# BatteryTestBoard_V1.net
KiCad netlist of a schematic drawn in EAGLE
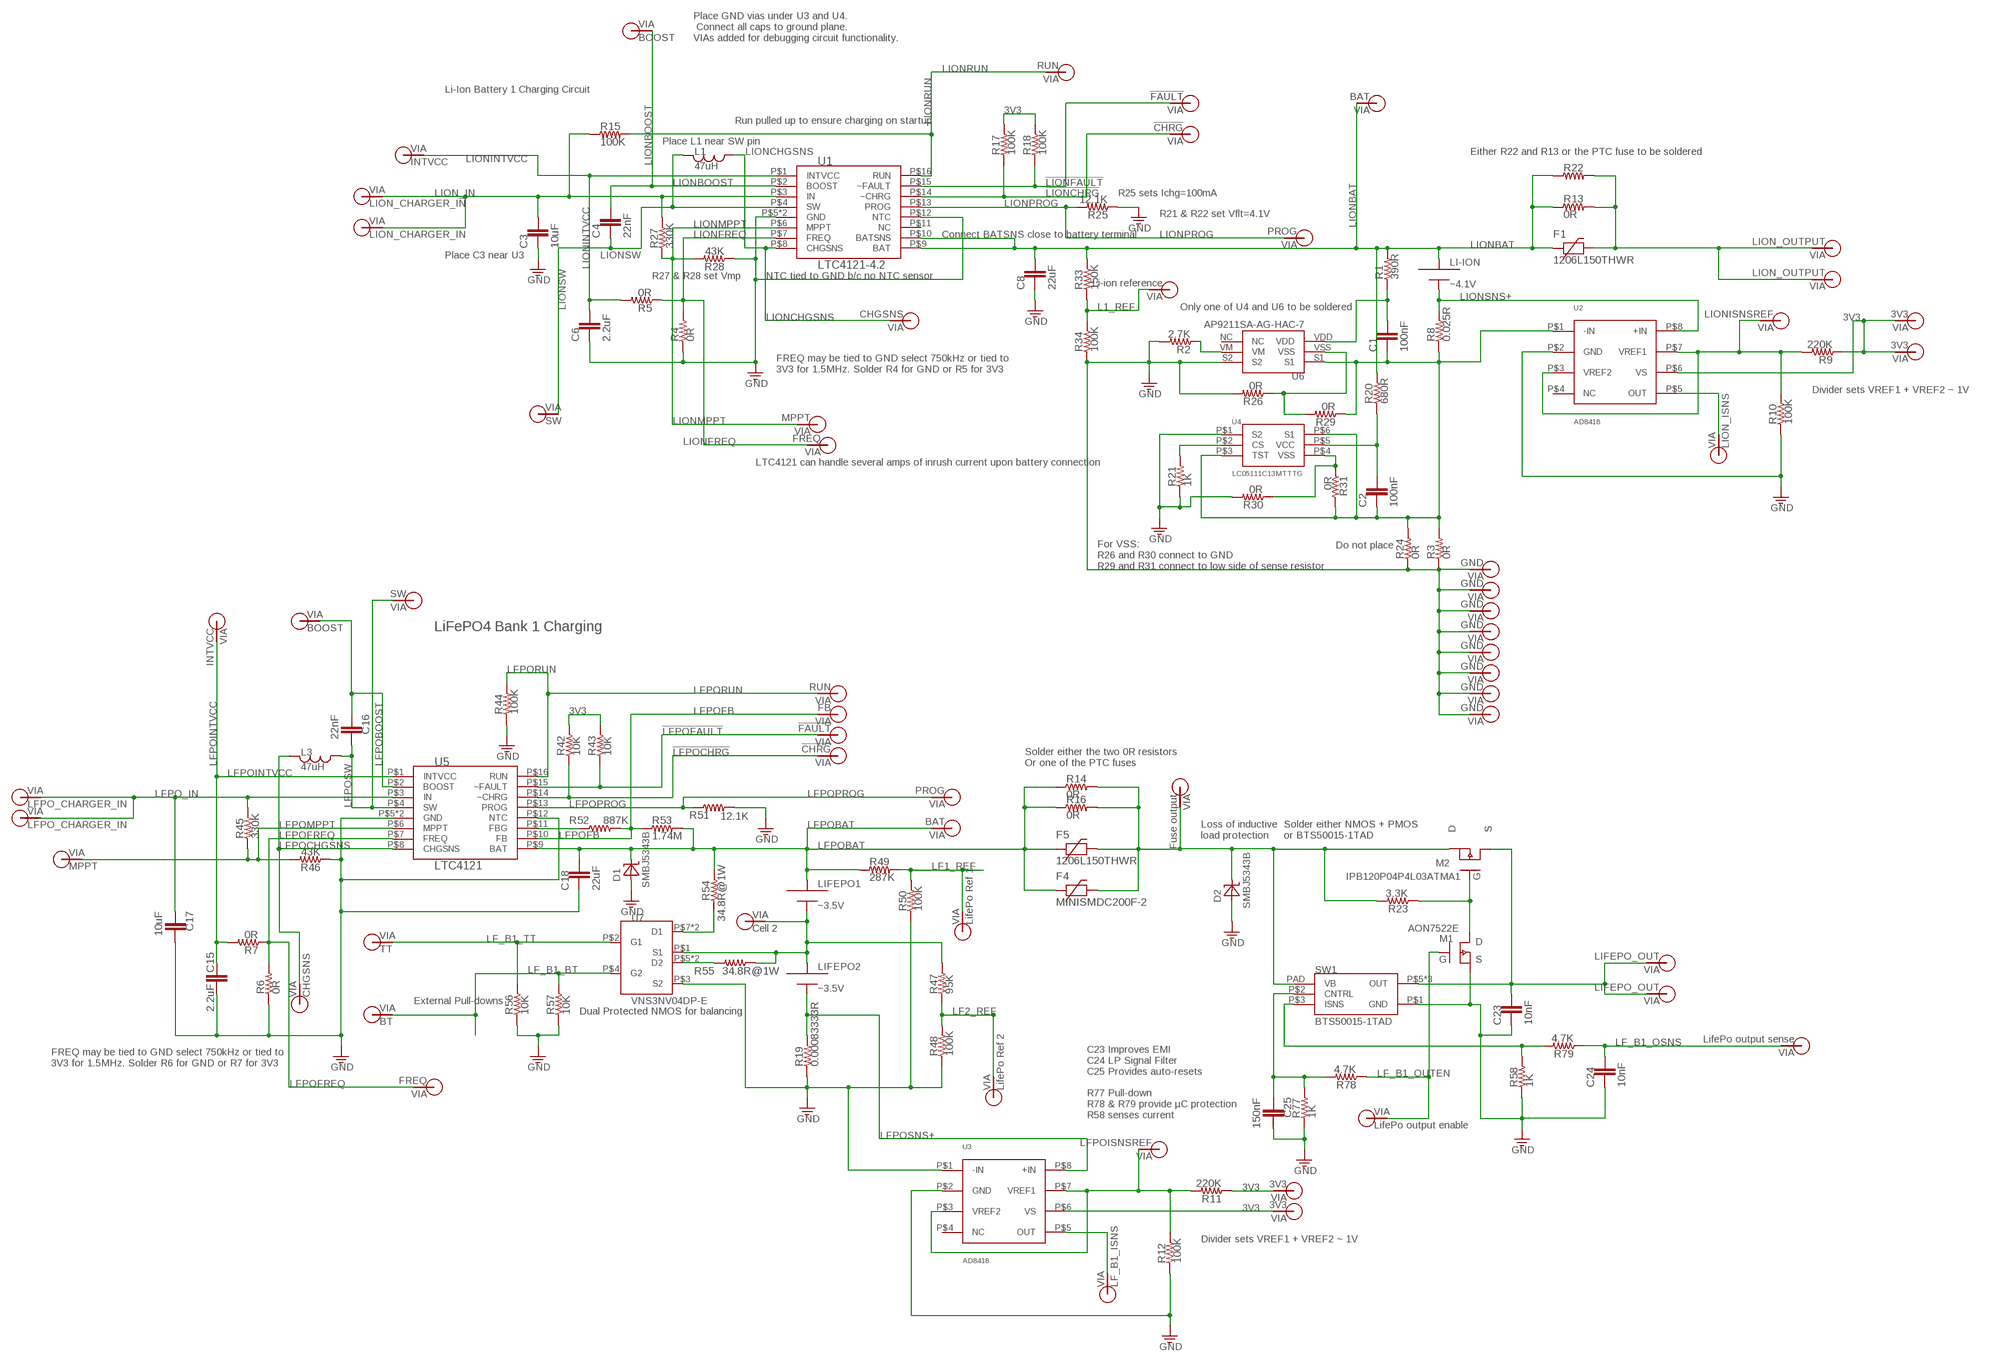
[diagram p0: schematic, sheet 1]

(export (version "E")
  (design (tool "Eeschema 10.0.6"))
  (components
    (comp (ref "C1")
      (value "100nF")
      (footprint "eagle-import:0805")
      (libsource (lib "eagle-import") (part "CAP0805"))
    )
    (comp (ref "C2")
      (value "100nF")
      (footprint "eagle-import:0805")
      (libsource (lib "eagle-import") (part "CAP0805"))
    )
    (comp (ref "C3")
      (value "10uF")
      (footprint "eagle-import:0805")
      (libsource (lib "eagle-import") (part "CAP0805"))
    )
    (comp (ref "C4")
      (value "22nF")
      (footprint "eagle-import:0805")
      (libsource (lib "eagle-import") (part "CAP0805"))
    )
    (comp (ref "C6")
      (value "2.2uF")
      (footprint "eagle-import:0805")
      (libsource (lib "eagle-import") (part "CAP0805"))
    )
    (comp (ref "C8")
      (value "22uF")
      (footprint "eagle-import:0805")
      (libsource (lib "eagle-import") (part "CAP0805"))
    )
    (comp (ref "C15")
      (value "2.2uF")
      (footprint "eagle-import:0805")
      (libsource (lib "eagle-import") (part "CAP0805"))
    )
    (comp (ref "C16")
      (value "22nF")
      (footprint "eagle-import:0805")
      (libsource (lib "eagle-import") (part "CAP0805"))
    )
    (comp (ref "C17")
      (value "10uF")
      (footprint "eagle-import:0805")
      (libsource (lib "eagle-import") (part "CAP0805"))
    )
    (comp (ref "C18")
      (value "22uF")
      (footprint "eagle-import:0805")
      (libsource (lib "eagle-import") (part "CAP0805"))
    )
    (comp (ref "C23")
      (value "10nF")
      (footprint "eagle-import:0805")
      (libsource (lib "eagle-import") (part "CAP0805"))
    )
    (comp (ref "C24")
      (value "10nF")
      (footprint "eagle-import:0805")
      (libsource (lib "eagle-import") (part "CAP0805"))
    )
    (comp (ref "C25")
      (value "150nF")
      (footprint "eagle-import:0805")
      (libsource (lib "eagle-import") (part "CAP0805"))
    )
    (comp (ref "D1")
      (value "SMBJ5343B")
      (footprint "eagle-import:DO214AA")
      (libsource (lib "eagle-import") (part "SMBJ5343B"))
    )
    (comp (ref "D2")
      (value "SMBJ5343B")
      (footprint "eagle-import:DO214AA")
      (libsource (lib "eagle-import") (part "SMBJ5343B"))
    )
    (comp (ref "F1")
      (value "1206L150THWR")
      (footprint "eagle-import:1206")
      (libsource (lib "eagle-import") (part "1206L150THWR"))
    )
    (comp (ref "F4")
      (value "MINISMDC200F-2")
      (footprint "eagle-import:1812")
      (libsource (lib "eagle-import") (part "MINISMDC200F-2"))
    )
    (comp (ref "F5")
      (value "1206L150THWR")
      (footprint "eagle-import:1206")
      (libsource (lib "eagle-import") (part "1206L150THWR"))
    )
    (comp (ref "L1")
      (value "47uH")
      (footprint "eagle-import:1812")
      (libsource (lib "eagle-import") (part "IND1812"))
    )
    (comp (ref "L3")
      (value "47uH")
      (footprint "eagle-import:1812")
      (libsource (lib "eagle-import") (part "IND1812"))
    )
    (comp (ref "LI-ION")
      (value "~4.1V")
      (footprint "eagle-import:EQUISAT-BATTERY-VA")
      (libsource (lib "eagle-import") (part "LI-ION"))
    )
    (comp (ref "LIFEPO1")
      (value "~3.5V")
      (footprint "eagle-import:EQUISAT-BATTERY-VA")
      (libsource (lib "eagle-import") (part "LIFEPO4VA"))
    )
    (comp (ref "LIFEPO2")
      (value "~3.5V")
      (footprint "eagle-import:EQUISAT-BATTERY-VA")
      (libsource (lib "eagle-import") (part "LIFEPO4VA"))
    )
    (comp (ref "M1")
      (value "AON7522E")
      (footprint "eagle-import:DFN-3X3-8")
      (libsource (lib "eagle-import") (part "AON7522E"))
    )
    (comp (ref "M2")
      (value "IPB120P04P4L03ATMA1")
      (footprint "eagle-import:TO263")
      (libsource (lib "eagle-import") (part "IPB120P04P4L03ATMA1"))
    )
    (comp (ref "R1")
      (value "390R")
      (footprint "eagle-import:0805")
      (libsource (lib "eagle-import") (part "RES0805"))
    )
    (comp (ref "R2")
      (value "2.7K")
      (footprint "eagle-import:0805")
      (libsource (lib "eagle-import") (part "RES0805"))
    )
    (comp (ref "R3")
      (value "0R")
      (footprint "eagle-import:1210")
      (libsource (lib "eagle-import") (part "RES1210"))
    )
    (comp (ref "R4")
      (value "0R")
      (footprint "eagle-import:0805")
      (libsource (lib "eagle-import") (part "RES0805"))
    )
    (comp (ref "R5")
      (value "0R")
      (footprint "eagle-import:0805")
      (libsource (lib "eagle-import") (part "RES0805"))
    )
    (comp (ref "R6")
      (value "0R")
      (footprint "eagle-import:0805")
      (libsource (lib "eagle-import") (part "RES0805"))
    )
    (comp (ref "R7")
      (value "0R")
      (footprint "eagle-import:0805")
      (libsource (lib "eagle-import") (part "RES0805"))
    )
    (comp (ref "R8")
      (value "0.025R")
      (footprint "eagle-import:1210")
      (libsource (lib "eagle-import") (part "RES1210"))
    )
    (comp (ref "R9")
      (value "220K")
      (footprint "eagle-import:0805")
      (libsource (lib "eagle-import") (part "RES0805"))
    )
    (comp (ref "R10")
      (value "100K")
      (footprint "eagle-import:0805")
      (libsource (lib "eagle-import") (part "RES0805"))
    )
    (comp (ref "R11")
      (value "220K")
      (footprint "eagle-import:0805")
      (libsource (lib "eagle-import") (part "RES0805"))
    )
    (comp (ref "R12")
      (value "100K")
      (footprint "eagle-import:0805")
      (libsource (lib "eagle-import") (part "RES0805"))
    )
    (comp (ref "R13")
      (value "0R")
      (footprint "eagle-import:1210")
      (libsource (lib "eagle-import") (part "RES1210"))
    )
    (comp (ref "R14")
      (value "0R")
      (footprint "eagle-import:1210")
      (libsource (lib "eagle-import") (part "RES1210"))
    )
    (comp (ref "R15")
      (value "100K")
      (footprint "eagle-import:0805")
      (libsource (lib "eagle-import") (part "RES0805"))
    )
    (comp (ref "R16")
      (value "0R")
      (footprint "eagle-import:1210")
      (libsource (lib "eagle-import") (part "RES1210"))
    )
    (comp (ref "R17")
      (value "100K")
      (footprint "eagle-import:0805")
      (libsource (lib "eagle-import") (part "RES0805"))
    )
    (comp (ref "R18")
      (value "100K")
      (footprint "eagle-import:0805")
      (libsource (lib "eagle-import") (part "RES0805"))
    )
    (comp (ref "R19")
      (value "0.00083333R")
      (footprint "eagle-import:1210")
      (libsource (lib "eagle-import") (part "RES1210"))
    )
    (comp (ref "R20")
      (value "680R")
      (footprint "eagle-import:0805")
      (libsource (lib "eagle-import") (part "RES0805"))
    )
    (comp (ref "R21")
      (value "1K")
      (footprint "eagle-import:0805")
      (libsource (lib "eagle-import") (part "RES0805"))
    )
    (comp (ref "R22")
      (value "0R")
      (footprint "eagle-import:1210")
      (libsource (lib "eagle-import") (part "RES1210"))
    )
    (comp (ref "R23")
      (value "3.3K")
      (footprint "eagle-import:0805")
      (libsource (lib "eagle-import") (part "RES0805"))
    )
    (comp (ref "R24")
      (value "0R")
      (footprint "eagle-import:1210")
      (libsource (lib "eagle-import") (part "RES1210"))
    )
    (comp (ref "R25")
      (value "12.1K")
      (footprint "eagle-import:0805")
      (libsource (lib "eagle-import") (part "RES0805"))
    )
    (comp (ref "R26")
      (value "0R")
      (footprint "eagle-import:0805")
      (libsource (lib "eagle-import") (part "RES0805"))
    )
    (comp (ref "R27")
      (value "330K")
      (footprint "eagle-import:0805")
      (libsource (lib "eagle-import") (part "RES0805"))
    )
    (comp (ref "R28")
      (value "43K")
      (footprint "eagle-import:0805")
      (libsource (lib "eagle-import") (part "RES0805"))
    )
    (comp (ref "R29")
      (value "0R")
      (footprint "eagle-import:0805")
      (libsource (lib "eagle-import") (part "RES0805"))
    )
    (comp (ref "R30")
      (value "0R")
      (footprint "eagle-import:0805")
      (libsource (lib "eagle-import") (part "RES0805"))
    )
    (comp (ref "R31")
      (value "0R")
      (footprint "eagle-import:0805")
      (libsource (lib "eagle-import") (part "RES0805"))
    )
    (comp (ref "R33")
      (value "150K")
      (footprint "eagle-import:0805")
      (libsource (lib "eagle-import") (part "RES0805"))
    )
    (comp (ref "R34")
      (value "100K")
      (footprint "eagle-import:0805")
      (libsource (lib "eagle-import") (part "RES0805"))
    )
    (comp (ref "R42")
      (value "10K")
      (footprint "eagle-import:0805")
      (libsource (lib "eagle-import") (part "RES0805"))
    )
    (comp (ref "R43")
      (value "10K")
      (footprint "eagle-import:0805")
      (libsource (lib "eagle-import") (part "RES0805"))
    )
    (comp (ref "R44")
      (value "100K")
      (footprint "eagle-import:0805")
      (libsource (lib "eagle-import") (part "RES0805"))
    )
    (comp (ref "R45")
      (value "330K")
      (footprint "eagle-import:0805")
      (libsource (lib "eagle-import") (part "RES0805"))
    )
    (comp (ref "R46")
      (value "43K")
      (footprint "eagle-import:0805")
      (libsource (lib "eagle-import") (part "RES0805"))
    )
    (comp (ref "R47")
      (value "95K")
      (footprint "eagle-import:0805")
      (libsource (lib "eagle-import") (part "RES0805"))
    )
    (comp (ref "R48")
      (value "100K")
      (footprint "eagle-import:0805")
      (libsource (lib "eagle-import") (part "RES0805"))
    )
    (comp (ref "R49")
      (value "287K")
      (footprint "eagle-import:0805")
      (libsource (lib "eagle-import") (part "RES0805"))
    )
    (comp (ref "R50")
      (value "100K")
      (footprint "eagle-import:0805")
      (libsource (lib "eagle-import") (part "RES0805"))
    )
    (comp (ref "R51")
      (value "12.1K")
      (footprint "eagle-import:0805")
      (libsource (lib "eagle-import") (part "RES0805"))
    )
    (comp (ref "R52")
      (value "887K")
      (footprint "eagle-import:0805")
      (libsource (lib "eagle-import") (part "RES0805"))
    )
    (comp (ref "R53")
      (value "1.74M")
      (footprint "eagle-import:0805")
      (libsource (lib "eagle-import") (part "RES0805"))
    )
    (comp (ref "R54")
      (value "34.8R@1W")
      (footprint "eagle-import:1210")
      (libsource (lib "eagle-import") (part "RES1210"))
    )
    (comp (ref "R55")
      (value "34.8R@1W")
      (footprint "eagle-import:1210")
      (libsource (lib "eagle-import") (part "RES1210"))
    )
    (comp (ref "R56")
      (value "10K")
      (footprint "eagle-import:0805")
      (libsource (lib "eagle-import") (part "RES0805"))
    )
    (comp (ref "R57")
      (value "10K")
      (footprint "eagle-import:0805")
      (libsource (lib "eagle-import") (part "RES0805"))
    )
    (comp (ref "R58")
      (value "1K")
      (footprint "eagle-import:0805")
      (libsource (lib "eagle-import") (part "RES0805"))
    )
    (comp (ref "R77")
      (value "1K")
      (footprint "eagle-import:0805")
      (libsource (lib "eagle-import") (part "RES0805"))
    )
    (comp (ref "R78")
      (value "4.7K")
      (footprint "eagle-import:0805")
      (libsource (lib "eagle-import") (part "RES0805"))
    )
    (comp (ref "R79")
      (value "4.7K")
      (footprint "eagle-import:0805")
      (libsource (lib "eagle-import") (part "RES0805"))
    )
    (comp (ref "SW1")
      (value "BTS50015-1TAD")
      (footprint "eagle-import:TO-263-7-8")
      (libsource (lib "eagle-import") (part "BTS50015-1TAD"))
    )
    (comp (ref "U1")
      (value "LTC4121-4.2")
      (footprint "eagle-import:QFN-16-PAD")
      (libsource (lib "eagle-import") (part "LTC4121-4.2"))
    )
    (comp (ref "U2")
      (value "AD8418")
      (footprint "eagle-import:MSOP-8")
      (libsource (lib "eagle-import") (part "AD8418"))
    )
    (comp (ref "U3")
      (value "AD8418")
      (footprint "eagle-import:MSOP-8")
      (libsource (lib "eagle-import") (part "AD8418"))
    )
    (comp (ref "U4")
      (value "LC05111C13MTTTG")
      (footprint "eagle-import:WDFN6")
      (libsource (lib "eagle-import") (part "LC05111C13MTTTG"))
    )
    (comp (ref "U5")
      (value "LTC4121")
      (footprint "eagle-import:QFN-16-PAD")
      (libsource (lib "eagle-import") (part "LTC4121"))
    )
    (comp (ref "U6")
      (value "AP9211SA-AG-HAC-7")
      (footprint "eagle-import:U-DFN2030-6")
      (libsource (lib "eagle-import") (part "AP9211SA-AG-HAC-7"))
    )
    (comp (ref "U7")
      (value "VNS3NV04DP-E")
      (footprint "eagle-import:SO-8")
      (libsource (lib "eagle-import") (part "VNS3NV04DP-E"))
    )
    (comp (ref "V1")
      (value "LION_OUTPUT")
      (footprint "eagle-import:VIA-120MIL")
      (libsource (lib "eagle-import") (part "VIA-120MIL"))
    )
    (comp (ref "V2")
      (value "Fuse output")
      (footprint "eagle-import:VIA-60MIL-SQ")
      (libsource (lib "eagle-import") (part "VIA60MIL-SQ"))
    )
    (comp (ref "V3")
      (value "GND")
      (footprint "eagle-import:VIA-60MIL-SQ")
      (libsource (lib "eagle-import") (part "VIA60MIL-SQ"))
    )
    (comp (ref "V4")
      (value "GND")
      (footprint "eagle-import:VIA-60MIL-SQ")
      (libsource (lib "eagle-import") (part "VIA60MIL-SQ"))
    )
    (comp (ref "V5")
      (value "GND")
      (footprint "eagle-import:VIA-60MIL-SQ")
      (libsource (lib "eagle-import") (part "VIA60MIL-SQ"))
    )
    (comp (ref "V6")
      (value "GND")
      (footprint "eagle-import:VIA-60MIL-SQ")
      (libsource (lib "eagle-import") (part "VIA60MIL-SQ"))
    )
    (comp (ref "V7")
      (value "GND")
      (footprint "eagle-import:VIA-60MIL-SQ")
      (libsource (lib "eagle-import") (part "VIA60MIL-SQ"))
    )
    (comp (ref "V8")
      (value "GND")
      (footprint "eagle-import:VIA-60MIL-SQ")
      (libsource (lib "eagle-import") (part "VIA60MIL-SQ"))
    )
    (comp (ref "V9")
      (value "LFPO_CHARGER_IN")
      (footprint "eagle-import:VIA-60MIL-SQ")
      (libsource (lib "eagle-import") (part "VIA60MIL-SQ"))
    )
    (comp (ref "V10")
      (value "GND")
      (footprint "eagle-import:VIA-60MIL-SQ")
      (libsource (lib "eagle-import") (part "VIA60MIL-SQ"))
    )
    (comp (ref "V11")
      (value "LFPOISNSREF")
      (footprint "eagle-import:VIA-60MIL-SQ")
      (libsource (lib "eagle-import") (part "VIA60MIL-SQ"))
    )
    (comp (ref "V12")
      (value "LIONISNSREF")
      (footprint "eagle-import:VIA-60MIL-SQ")
      (libsource (lib "eagle-import") (part "VIA60MIL-SQ"))
    )
    (comp (ref "V13")
      (value "LF_B1_ISNS")
      (footprint "eagle-import:VIA-60MIL-SQ")
      (libsource (lib "eagle-import") (part "VIA60MIL-SQ"))
    )
    (comp (ref "V16")
      (value "Cell 2")
      (footprint "eagle-import:VIA-60MIL-SQ")
      (libsource (lib "eagle-import") (part "VIA60MIL-SQ"))
    )
    (comp (ref "V20")
      (value "LifePo output enable")
      (footprint "eagle-import:VIA-60MIL-SQ")
      (libsource (lib "eagle-import") (part "VIA60MIL-SQ"))
    )
    (comp (ref "V21")
      (value "LIFEPO_OUT")
      (footprint "eagle-import:VIA-120MIL")
      (libsource (lib "eagle-import") (part "VIA-120MIL"))
    )
    (comp (ref "V26")
      (value "LIFEPO_OUT")
      (footprint "eagle-import:VIA-120MIL")
      (libsource (lib "eagle-import") (part "VIA-120MIL"))
    )
    (comp (ref "V29")
      (value "TT")
      (footprint "eagle-import:VIA-60MIL-SQ")
      (libsource (lib "eagle-import") (part "VIA60MIL-SQ"))
    )
    (comp (ref "V31")
      (value "LifePo output sense")
      (footprint "eagle-import:VIA-60MIL-SQ")
      (libsource (lib "eagle-import") (part "VIA60MIL-SQ"))
    )
    (comp (ref "V32")
      (value "BT")
      (footprint "eagle-import:VIA-60MIL-SQ")
      (libsource (lib "eagle-import") (part "VIA60MIL-SQ"))
    )
    (comp (ref "V34")
      (value "LION_CHARGER_IN")
      (footprint "eagle-import:VIA-60MIL-SQ")
      (libsource (lib "eagle-import") (part "VIA60MIL-SQ"))
    )
    (comp (ref "V35")
      (value "LION_CHARGER_IN")
      (footprint "eagle-import:VIA-60MIL-SQ")
      (libsource (lib "eagle-import") (part "VIA60MIL-SQ"))
    )
    (comp (ref "V36")
      (value "BOOST")
      (footprint "eagle-import:VIA-60MIL-SQ")
      (libsource (lib "eagle-import") (part "VIA60MIL-SQ"))
    )
    (comp (ref "V37")
      (value "LION_OUTPUT")
      (footprint "eagle-import:VIA-120MIL")
      (libsource (lib "eagle-import") (part "VIA-120MIL"))
    )
    (comp (ref "V38")
      (value "SW")
      (footprint "eagle-import:VIA-60MIL-SQ")
      (libsource (lib "eagle-import") (part "VIA60MIL-SQ"))
    )
    (comp (ref "V39")
      (value "MPPT")
      (footprint "eagle-import:VIA-60MIL-SQ")
      (libsource (lib "eagle-import") (part "VIA60MIL-SQ"))
    )
    (comp (ref "V41")
      (value "GND")
      (footprint "eagle-import:VIA-60MIL-SQ")
      (libsource (lib "eagle-import") (part "VIA60MIL-SQ"))
    )
    (comp (ref "V43")
      (value "LION_ISNS")
      (footprint "eagle-import:VIA-60MIL-SQ")
      (libsource (lib "eagle-import") (part "VIA60MIL-SQ"))
    )
    (comp (ref "V44")
      (value "Li-ion reference")
      (footprint "eagle-import:VIA-60MIL-SQ")
      (libsource (lib "eagle-import") (part "VIA60MIL-SQ"))
    )
    (comp (ref "V46")
      (value "CHGSNS")
      (footprint "eagle-import:VIA-60MIL-SQ")
      (libsource (lib "eagle-import") (part "VIA60MIL-SQ"))
    )
    (comp (ref "V47")
      (value "FREQ")
      (footprint "eagle-import:VIA-60MIL-SQ")
      (libsource (lib "eagle-import") (part "VIA60MIL-SQ"))
    )
    (comp (ref "V48")
      (value "BAT")
      (footprint "eagle-import:VIA-60MIL-SQ")
      (libsource (lib "eagle-import") (part "VIA60MIL-SQ"))
    )
    (comp (ref "V50")
      (value "PROG")
      (footprint "eagle-import:VIA-60MIL-SQ")
      (libsource (lib "eagle-import") (part "VIA60MIL-SQ"))
    )
    (comp (ref "V51")
      (value "!CHRG")
      (footprint "eagle-import:VIA-60MIL-SQ")
      (libsource (lib "eagle-import") (part "VIA60MIL-SQ"))
    )
    (comp (ref "V52")
      (value "!FAULT")
      (footprint "eagle-import:VIA-60MIL-SQ")
      (libsource (lib "eagle-import") (part "VIA60MIL-SQ"))
    )
    (comp (ref "V53")
      (value "RUN")
      (footprint "eagle-import:VIA-60MIL-SQ")
      (libsource (lib "eagle-import") (part "VIA60MIL-SQ"))
    )
    (comp (ref "V54")
      (value "BOOST")
      (footprint "eagle-import:VIA-60MIL-SQ")
      (libsource (lib "eagle-import") (part "VIA60MIL-SQ"))
    )
    (comp (ref "V55")
      (value "INTVCC")
      (footprint "eagle-import:VIA-60MIL-SQ")
      (libsource (lib "eagle-import") (part "VIA60MIL-SQ"))
    )
    (comp (ref "V57")
      (value "SW")
      (footprint "eagle-import:VIA-60MIL-SQ")
      (libsource (lib "eagle-import") (part "VIA60MIL-SQ"))
    )
    (comp (ref "V58")
      (value "LifePo Ref 1")
      (footprint "eagle-import:VIA-60MIL-SQ")
      (libsource (lib "eagle-import") (part "VIA60MIL-SQ"))
    )
    (comp (ref "V59")
      (value "LifePo Ref 2")
      (footprint "eagle-import:VIA-60MIL-SQ")
      (libsource (lib "eagle-import") (part "VIA60MIL-SQ"))
    )
    (comp (ref "V60")
      (value "MPPT")
      (footprint "eagle-import:VIA-60MIL-SQ")
      (libsource (lib "eagle-import") (part "VIA60MIL-SQ"))
    )
    (comp (ref "V61")
      (value "CHGSNS")
      (footprint "eagle-import:VIA-60MIL-SQ")
      (libsource (lib "eagle-import") (part "VIA60MIL-SQ"))
    )
    (comp (ref "V62")
      (value "FREQ")
      (footprint "eagle-import:VIA-60MIL-SQ")
      (libsource (lib "eagle-import") (part "VIA60MIL-SQ"))
    )
    (comp (ref "V63")
      (value "BAT")
      (footprint "eagle-import:VIA-60MIL-SQ")
      (libsource (lib "eagle-import") (part "VIA60MIL-SQ"))
    )
    (comp (ref "V65")
      (value "PROG")
      (footprint "eagle-import:VIA-60MIL-SQ")
      (libsource (lib "eagle-import") (part "VIA60MIL-SQ"))
    )
    (comp (ref "V66")
      (value "!CHRG")
      (footprint "eagle-import:VIA-60MIL-SQ")
      (libsource (lib "eagle-import") (part "VIA60MIL-SQ"))
    )
    (comp (ref "V67")
      (value "!FAULT")
      (footprint "eagle-import:VIA-60MIL-SQ")
      (libsource (lib "eagle-import") (part "VIA60MIL-SQ"))
    )
    (comp (ref "V68")
      (value "RUN")
      (footprint "eagle-import:VIA-60MIL-SQ")
      (libsource (lib "eagle-import") (part "VIA60MIL-SQ"))
    )
    (comp (ref "V69")
      (value "INTVCC")
      (footprint "eagle-import:VIA-60MIL-SQ")
      (libsource (lib "eagle-import") (part "VIA60MIL-SQ"))
    )
    (comp (ref "V70")
      (value "FB")
      (footprint "eagle-import:VIA-60MIL-SQ")
      (libsource (lib "eagle-import") (part "VIA60MIL-SQ"))
    )
    (comp (ref "V71")
      (value "3V3")
      (footprint "eagle-import:VIA-60MIL-SQ")
      (libsource (lib "eagle-import") (part "VIA60MIL-SQ"))
    )
    (comp (ref "V72")
      (value "3V3")
      (footprint "eagle-import:VIA-60MIL-SQ")
      (libsource (lib "eagle-import") (part "VIA60MIL-SQ"))
    )
    (comp (ref "V73")
      (value "3V3")
      (footprint "eagle-import:VIA-60MIL-SQ")
      (libsource (lib "eagle-import") (part "VIA60MIL-SQ"))
    )
    (comp (ref "V74")
      (value "3V3")
      (footprint "eagle-import:VIA-60MIL-SQ")
      (libsource (lib "eagle-import") (part "VIA60MIL-SQ"))
    )
    (comp (ref "V75")
      (value "LFPO_CHARGER_IN")
      (footprint "eagle-import:VIA-60MIL-SQ")
      (libsource (lib "eagle-import") (part "VIA60MIL-SQ"))
    )
  )
  (nets
    (net (code "1") (name "/3V3") (class "Default")
      (node (ref "R11") (pin "1") (pinfunction "1_1") (pintype "passive"))
      (node (ref "R17") (pin "2") (pinfunction "2_2") (pintype "passive"))
      (node (ref "R18") (pin "2") (pinfunction "2_2") (pintype "passive"))
      (node (ref "R42") (pin "2") (pinfunction "2_2") (pintype "passive"))
      (node (ref "R43") (pin "2") (pinfunction "2_2") (pintype "passive"))
      (node (ref "R9") (pin "1") (pinfunction "1_1") (pintype "passive"))
      (node (ref "U2") (pin "P$6") (pinfunction "VS_P$6") (pintype "bidirectional"))
      (node (ref "U3") (pin "P$6") (pinfunction "VS_P$6") (pintype "bidirectional"))
      (node (ref "V71") (pin "P$1") (pinfunction "P$1_P$1") (pintype "bidirectional"))
      (node (ref "V72") (pin "P$1") (pinfunction "P$1_P$1") (pintype "bidirectional"))
      (node (ref "V73") (pin "P$1") (pinfunction "P$1_P$1") (pintype "bidirectional"))
      (node (ref "V74") (pin "P$1") (pinfunction "P$1_P$1") (pintype "bidirectional"))
    )
    (net (code "2") (name "/L1_REF") (class "Default")
      (node (ref "R33") (pin "1") (pinfunction "1_1") (pintype "passive"))
      (node (ref "R34") (pin "2") (pinfunction "2_2") (pintype "passive"))
      (node (ref "V44") (pin "P$1") (pinfunction "P$1_P$1") (pintype "bidirectional"))
    )
    (net (code "3") (name "/LF1_REF") (class "Default")
      (node (ref "R49") (pin "2") (pinfunction "2_2") (pintype "passive"))
      (node (ref "R50") (pin "2") (pinfunction "2_2") (pintype "passive"))
      (node (ref "V58") (pin "P$1") (pinfunction "P$1_P$1") (pintype "bidirectional"))
    )
    (net (code "4") (name "/LF2_REF") (class "Default")
      (node (ref "R47") (pin "1") (pinfunction "1_1") (pintype "passive"))
      (node (ref "R48") (pin "2") (pinfunction "2_2") (pintype "passive"))
      (node (ref "V59") (pin "P$1") (pinfunction "P$1_P$1") (pintype "bidirectional"))
    )
    (net (code "5") (name "/LFPOBAT") (class "Default")
      (node (ref "C18") (pin "1") (pinfunction "P$1_1") (pintype "passive"))
      (node (ref "D1") (pin "C") (pinfunction "C_C") (pintype "passive"))
      (node (ref "F4") (pin "P$1") (pinfunction "P$1_P$1") (pintype "passive"))
      (node (ref "F5") (pin "1") (pinfunction "P$1_1") (pintype "passive"))
      (node (ref "LIFEPO1") (pin "PLUS") (pinfunction "PLUS_PLUS") (pintype "power_in"))
      (node (ref "R14") (pin "P$1") (pinfunction "1_P$1") (pintype "passive"))
      (node (ref "R16") (pin "P$1") (pinfunction "1_P$1") (pintype "passive"))
      (node (ref "R49") (pin "1") (pinfunction "1_1") (pintype "passive"))
      (node (ref "R53") (pin "2") (pinfunction "2_2") (pintype "passive"))
      (node (ref "R54") (pin "P$2") (pinfunction "2_P$2") (pintype "passive"))
      (node (ref "U5") (pin "P$9") (pinfunction "BAT_P$9") (pintype "bidirectional"))
      (node (ref "V63") (pin "P$1") (pinfunction "P$1_P$1") (pintype "bidirectional"))
    )
    (net (code "6") (name "/LFPOBOOST") (class "Default")
      (node (ref "C16") (pin "2") (pinfunction "P$2_2") (pintype "passive"))
      (node (ref "U5") (pin "P$2") (pinfunction "BOOST_P$2") (pintype "bidirectional"))
      (node (ref "V54") (pin "P$1") (pinfunction "P$1_P$1") (pintype "bidirectional"))
    )
    (net (code "7") (name "/LFPOCHGSNS") (class "Default")
      (node (ref "L3") (pin "P$1") (pinfunction "P$1_P$1") (pintype "passive"))
      (node (ref "U5") (pin "P$8") (pinfunction "CHGSNS_P$8") (pintype "bidirectional"))
      (node (ref "V61") (pin "P$1") (pinfunction "P$1_P$1") (pintype "bidirectional"))
    )
    (net (code "8") (name "/LFPOFB") (class "Default")
      (node (ref "R52") (pin "2") (pinfunction "2_2") (pintype "passive"))
      (node (ref "R53") (pin "1") (pinfunction "1_1") (pintype "passive"))
      (node (ref "U5") (pin "P$10") (pinfunction "FB_P$10") (pintype "bidirectional"))
      (node (ref "V70") (pin "P$1") (pinfunction "P$1_P$1") (pintype "bidirectional"))
    )
    (net (code "9") (name "/LFPOFREQ") (class "Default")
      (node (ref "R6") (pin "2") (pinfunction "2_2") (pintype "passive"))
      (node (ref "R7") (pin "1") (pinfunction "1_1") (pintype "passive"))
      (node (ref "U5") (pin "P$7") (pinfunction "FREQ_P$7") (pintype "bidirectional"))
      (node (ref "V62") (pin "P$1") (pinfunction "P$1_P$1") (pintype "bidirectional"))
    )
    (net (code "10") (name "/LFPOINTVCC") (class "Default")
      (node (ref "C15") (pin "2") (pinfunction "P$2_2") (pintype "passive"))
      (node (ref "R7") (pin "2") (pinfunction "2_2") (pintype "passive"))
      (node (ref "U5") (pin "P$1") (pinfunction "INTVCC_P$1") (pintype "bidirectional"))
      (node (ref "V69") (pin "P$1") (pinfunction "P$1_P$1") (pintype "bidirectional"))
    )
    (net (code "11") (name "/LFPOMPPT") (class "Default")
      (node (ref "R45") (pin "1") (pinfunction "1_1") (pintype "passive"))
      (node (ref "R46") (pin "2") (pinfunction "2_2") (pintype "passive"))
      (node (ref "U5") (pin "P$6") (pinfunction "MPPT_P$6") (pintype "bidirectional"))
      (node (ref "V60") (pin "P$1") (pinfunction "P$1_P$1") (pintype "bidirectional"))
    )
    (net (code "12") (name "/LFPOPROG") (class "Default")
      (node (ref "R51") (pin "1") (pinfunction "1_1") (pintype "passive"))
      (node (ref "U5") (pin "P$13") (pinfunction "PROG_P$13") (pintype "bidirectional"))
      (node (ref "V65") (pin "P$1") (pinfunction "P$1_P$1") (pintype "bidirectional"))
    )
    (net (code "13") (name "/LFPORUN") (class "Default")
      (node (ref "R44") (pin "2") (pinfunction "2_2") (pintype "passive"))
      (node (ref "U5") (pin "P$16") (pinfunction "RUN_P$16") (pintype "bidirectional"))
      (node (ref "V68") (pin "P$1") (pinfunction "P$1_P$1") (pintype "bidirectional"))
    )
    (net (code "14") (name "/LFPOSNS+") (class "Default")
      (node (ref "LIFEPO2") (pin "MINUS") (pinfunction "MINUS_MINUS") (pintype "power_in"))
      (node (ref "R19") (pin "P$2") (pinfunction "2_P$2") (pintype "passive"))
      (node (ref "U3") (pin "P$8") (pinfunction "+IN_P$8") (pintype "bidirectional"))
    )
    (net (code "15") (name "/LFPOSW") (class "Default")
      (node (ref "C16") (pin "1") (pinfunction "P$1_1") (pintype "passive"))
      (node (ref "L3") (pin "P$2") (pinfunction "P$2_P$2") (pintype "passive"))
      (node (ref "U5") (pin "P$4") (pinfunction "SW_P$4") (pintype "bidirectional"))
      (node (ref "V57") (pin "P$1") (pinfunction "P$1_P$1") (pintype "bidirectional"))
    )
    (net (code "16") (name "/LFPO_IN") (class "Default")
      (node (ref "C17") (pin "2") (pinfunction "P$2_2") (pintype "passive"))
      (node (ref "R45") (pin "2") (pinfunction "2_2") (pintype "passive"))
      (node (ref "U5") (pin "P$3") (pinfunction "IN_P$3") (pintype "bidirectional"))
      (node (ref "V75") (pin "P$1") (pinfunction "P$1_P$1") (pintype "bidirectional"))
      (node (ref "V9") (pin "P$1") (pinfunction "P$1_P$1") (pintype "bidirectional"))
    )
    (net (code "17") (name "/LF_B1_BT") (class "Default")
      (node (ref "R57") (pin "2") (pinfunction "2_2") (pintype "passive"))
      (node (ref "U7") (pin "P$4") (pinfunction "G2_P$4") (pintype "bidirectional"))
      (node (ref "V32") (pin "P$1") (pinfunction "P$1_P$1") (pintype "bidirectional"))
    )
    (net (code "18") (name "/LF_B1_OSNS") (class "Default")
      (node (ref "C24") (pin "1") (pinfunction "P$1_1") (pintype "passive"))
      (node (ref "R79") (pin "1") (pinfunction "1_1") (pintype "passive"))
      (node (ref "V31") (pin "P$1") (pinfunction "P$1_P$1") (pintype "bidirectional"))
    )
    (net (code "19") (name "/LF_B1_OUTEN") (class "Default")
      (node (ref "M1") (pin "P$4") (pinfunction "G_P$4") (pintype "bidirectional"))
      (node (ref "R78") (pin "1") (pinfunction "1_1") (pintype "passive"))
      (node (ref "V20") (pin "P$1") (pinfunction "P$1_P$1") (pintype "bidirectional"))
    )
    (net (code "20") (name "/LF_B1_TT") (class "Default")
      (node (ref "R56") (pin "2") (pinfunction "2_2") (pintype "passive"))
      (node (ref "U7") (pin "P$2") (pinfunction "G1_P$2") (pintype "bidirectional"))
      (node (ref "V29") (pin "P$1") (pinfunction "P$1_P$1") (pintype "bidirectional"))
    )
    (net (code "21") (name "/LIONBAT") (class "Default")
      (node (ref "C8") (pin "1") (pinfunction "P$1_1") (pintype "passive"))
      (node (ref "F1") (pin "1") (pinfunction "P$1_1") (pintype "passive"))
      (node (ref "LI-ION") (pin "PLUS") (pinfunction "PLUS_PLUS") (pintype "power_in"))
      (node (ref "R1") (pin "2") (pinfunction "2_2") (pintype "passive"))
      (node (ref "R13") (pin "P$1") (pinfunction "1_P$1") (pintype "passive"))
      (node (ref "R20") (pin "2") (pinfunction "2_2") (pintype "passive"))
      (node (ref "R22") (pin "P$1") (pinfunction "1_P$1") (pintype "passive"))
      (node (ref "R33") (pin "2") (pinfunction "2_2") (pintype "passive"))
      (node (ref "U1") (pin "P$10") (pinfunction "BATSNS_P$10") (pintype "bidirectional"))
      (node (ref "U1") (pin "P$9") (pinfunction "BAT_P$9") (pintype "bidirectional"))
      (node (ref "V48") (pin "P$1") (pinfunction "P$1_P$1") (pintype "bidirectional"))
    )
    (net (code "22") (name "/LIONBOOST") (class "Default")
      (node (ref "C4") (pin "1") (pinfunction "P$1_1") (pintype "passive"))
      (node (ref "U1") (pin "P$2") (pinfunction "BOOST_P$2") (pintype "bidirectional"))
      (node (ref "V36") (pin "P$1") (pinfunction "P$1_P$1") (pintype "bidirectional"))
    )
    (net (code "23") (name "/LIONCHGSNS") (class "Default")
      (node (ref "L1") (pin "P$2") (pinfunction "P$2_P$2") (pintype "passive"))
      (node (ref "U1") (pin "P$8") (pinfunction "CHGSNS_P$8") (pintype "bidirectional"))
      (node (ref "V46") (pin "P$1") (pinfunction "P$1_P$1") (pintype "bidirectional"))
    )
    (net (code "24") (name "/LIONFREQ") (class "Default")
      (node (ref "R4") (pin "2") (pinfunction "2_2") (pintype "passive"))
      (node (ref "R5") (pin "1") (pinfunction "1_1") (pintype "passive"))
      (node (ref "U1") (pin "P$7") (pinfunction "FREQ_P$7") (pintype "bidirectional"))
      (node (ref "V47") (pin "P$1") (pinfunction "P$1_P$1") (pintype "bidirectional"))
    )
    (net (code "25") (name "/LIONINTVCC") (class "Default")
      (node (ref "C6") (pin "1") (pinfunction "P$1_1") (pintype "passive"))
      (node (ref "R5") (pin "2") (pinfunction "2_2") (pintype "passive"))
      (node (ref "U1") (pin "P$1") (pinfunction "INTVCC_P$1") (pintype "bidirectional"))
      (node (ref "V55") (pin "P$1") (pinfunction "P$1_P$1") (pintype "bidirectional"))
    )
    (net (code "26") (name "/LIONMPPT") (class "Default")
      (node (ref "R27") (pin "1") (pinfunction "1_1") (pintype "passive"))
      (node (ref "R28") (pin "2") (pinfunction "2_2") (pintype "passive"))
      (node (ref "U1") (pin "P$6") (pinfunction "MPPT_P$6") (pintype "bidirectional"))
      (node (ref "V39") (pin "P$1") (pinfunction "P$1_P$1") (pintype "bidirectional"))
    )
    (net (code "27") (name "/LIONPROG") (class "Default")
      (node (ref "R25") (pin "2") (pinfunction "2_2") (pintype "passive"))
      (node (ref "U1") (pin "P$13") (pinfunction "PROG_P$13") (pintype "bidirectional"))
      (node (ref "V50") (pin "P$1") (pinfunction "P$1_P$1") (pintype "bidirectional"))
    )
    (net (code "28") (name "/LIONRUN") (class "Default")
      (node (ref "R15") (pin "2") (pinfunction "2_2") (pintype "passive"))
      (node (ref "U1") (pin "P$16") (pinfunction "RUN_P$16") (pintype "bidirectional"))
      (node (ref "V53") (pin "P$1") (pinfunction "P$1_P$1") (pintype "bidirectional"))
    )
    (net (code "29") (name "/LIONSNS+") (class "Default")
      (node (ref "LI-ION") (pin "MINUS") (pinfunction "MINUS_MINUS") (pintype "power_in"))
      (node (ref "R8") (pin "P$2") (pinfunction "2_P$2") (pintype "passive"))
      (node (ref "U2") (pin "P$8") (pinfunction "+IN_P$8") (pintype "bidirectional"))
    )
    (net (code "30") (name "/LIONSW") (class "Default")
      (node (ref "C4") (pin "2") (pinfunction "P$2_2") (pintype "passive"))
      (node (ref "L1") (pin "P$1") (pinfunction "P$1_P$1") (pintype "passive"))
      (node (ref "U1") (pin "P$4") (pinfunction "SW_P$4") (pintype "bidirectional"))
      (node (ref "V38") (pin "P$1") (pinfunction "P$1_P$1") (pintype "bidirectional"))
    )
    (net (code "31") (name "/LION_IN") (class "Default")
      (node (ref "C3") (pin "1") (pinfunction "P$1_1") (pintype "passive"))
      (node (ref "R15") (pin "1") (pinfunction "1_1") (pintype "passive"))
      (node (ref "R27") (pin "2") (pinfunction "2_2") (pintype "passive"))
      (node (ref "U1") (pin "P$3") (pinfunction "IN_P$3") (pintype "bidirectional"))
      (node (ref "V34") (pin "P$1") (pinfunction "P$1_P$1") (pintype "bidirectional"))
      (node (ref "V35") (pin "P$1") (pinfunction "P$1_P$1") (pintype "bidirectional"))
    )
    (net (code "32") (name "/~{LFPOCHRG}") (class "Default")
      (node (ref "R42") (pin "1") (pinfunction "1_1") (pintype "passive"))
      (node (ref "U5") (pin "P$14") (pinfunction "~{CHRG}_P$14") (pintype "bidirectional"))
      (node (ref "V66") (pin "P$1") (pinfunction "P$1_P$1") (pintype "bidirectional"))
    )
    (net (code "33") (name "/~{LFPOFAULT}") (class "Default")
      (node (ref "R43") (pin "1") (pinfunction "1_1") (pintype "passive"))
      (node (ref "U5") (pin "P$15") (pinfunction "~{FAULT}_P$15") (pintype "bidirectional"))
      (node (ref "V67") (pin "P$1") (pinfunction "P$1_P$1") (pintype "bidirectional"))
    )
    (net (code "34") (name "/~{LIONCHRG}") (class "Default")
      (node (ref "R17") (pin "1") (pinfunction "1_1") (pintype "passive"))
      (node (ref "U1") (pin "P$14") (pinfunction "~{CHRG}_P$14") (pintype "bidirectional"))
      (node (ref "V51") (pin "P$1") (pinfunction "P$1_P$1") (pintype "bidirectional"))
    )
    (net (code "35") (name "/~{LIONFAULT}") (class "Default")
      (node (ref "R18") (pin "1") (pinfunction "1_1") (pintype "passive"))
      (node (ref "U1") (pin "P$15") (pinfunction "~{FAULT}_P$15") (pintype "bidirectional"))
      (node (ref "V52") (pin "P$1") (pinfunction "P$1_P$1") (pintype "bidirectional"))
    )
    (net (code "36") (name "GND") (class "Default")
      (node (ref "C15") (pin "1") (pinfunction "P$1_1") (pintype "passive"))
      (node (ref "C17") (pin "1") (pinfunction "P$1_1") (pintype "passive"))
      (node (ref "C18") (pin "2") (pinfunction "P$2_2") (pintype "passive"))
      (node (ref "C23") (pin "2") (pinfunction "P$2_2") (pintype "passive"))
      (node (ref "C24") (pin "2") (pinfunction "P$2_2") (pintype "passive"))
      (node (ref "C25") (pin "1") (pinfunction "P$1_1") (pintype "passive"))
      (node (ref "C3") (pin "2") (pinfunction "P$2_2") (pintype "passive"))
      (node (ref "C6") (pin "2") (pinfunction "P$2_2") (pintype "passive"))
      (node (ref "C8") (pin "2") (pinfunction "P$2_2") (pintype "passive"))
      (node (ref "D1") (pin "A") (pinfunction "A_A") (pintype "passive"))
      (node (ref "D2") (pin "A") (pinfunction "A_A") (pintype "passive"))
      (node (ref "M1") (pin "P$1") (pinfunction "S_P$1") (pintype "bidirectional"))
      (node (ref "M1") (pin "P$2") (pinfunction "S_P$2") (pintype "bidirectional"))
      (node (ref "M1") (pin "P$3") (pinfunction "S_P$3") (pintype "bidirectional"))
      (node (ref "R10") (pin "1") (pinfunction "1_1") (pintype "passive"))
      (node (ref "R12") (pin "1") (pinfunction "1_1") (pintype "passive"))
      (node (ref "R19") (pin "P$1") (pinfunction "1_P$1") (pintype "passive"))
      (node (ref "R2") (pin "2") (pinfunction "2_2") (pintype "passive"))
      (node (ref "R21") (pin "1") (pinfunction "1_1") (pintype "passive"))
      (node (ref "R24") (pin "P$1") (pinfunction "1_P$1") (pintype "passive"))
      (node (ref "R25") (pin "1") (pinfunction "1_1") (pintype "passive"))
      (node (ref "R26") (pin "2") (pinfunction "2_2") (pintype "passive"))
      (node (ref "R28") (pin "1") (pinfunction "1_1") (pintype "passive"))
      (node (ref "R3") (pin "P$1") (pinfunction "1_P$1") (pintype "passive"))
      (node (ref "R30") (pin "2") (pinfunction "2_2") (pintype "passive"))
      (node (ref "R34") (pin "1") (pinfunction "1_1") (pintype "passive"))
      (node (ref "R4") (pin "1") (pinfunction "1_1") (pintype "passive"))
      (node (ref "R44") (pin "1") (pinfunction "1_1") (pintype "passive"))
      (node (ref "R46") (pin "1") (pinfunction "1_1") (pintype "passive"))
      (node (ref "R48") (pin "1") (pinfunction "1_1") (pintype "passive"))
      (node (ref "R50") (pin "1") (pinfunction "1_1") (pintype "passive"))
      (node (ref "R51") (pin "2") (pinfunction "2_2") (pintype "passive"))
      (node (ref "R56") (pin "1") (pinfunction "1_1") (pintype "passive"))
      (node (ref "R57") (pin "1") (pinfunction "1_1") (pintype "passive"))
      (node (ref "R58") (pin "1") (pinfunction "1_1") (pintype "passive"))
      (node (ref "R6") (pin "1") (pinfunction "1_1") (pintype "passive"))
      (node (ref "R77") (pin "1") (pinfunction "1_1") (pintype "passive"))
      (node (ref "SW1") (pin "P$1") (pinfunction "GND_P$1") (pintype "bidirectional"))
      (node (ref "U1") (pin "P$12") (pinfunction "NTC_P$12") (pintype "bidirectional"))
      (node (ref "U1") (pin "P$17") (pinfunction "GND_P$17") (pintype "bidirectional"))
      (node (ref "U1") (pin "P$5") (pinfunction "GND_P$5") (pintype "bidirectional"))
      (node (ref "U2") (pin "P$2") (pinfunction "GND_P$2") (pintype "bidirectional"))
      (node (ref "U3") (pin "P$1") (pinfunction "-IN_P$1") (pintype "bidirectional"))
      (node (ref "U3") (pin "P$2") (pinfunction "GND_P$2") (pintype "bidirectional"))
      (node (ref "U4") (pin "P$1") (pinfunction "S2_P$1") (pintype "bidirectional"))
      (node (ref "U5") (pin "P$12") (pinfunction "NTC_P$12") (pintype "bidirectional"))
      (node (ref "U5") (pin "P$17") (pinfunction "GND_P$17") (pintype "bidirectional"))
      (node (ref "U5") (pin "P$5") (pinfunction "GND_P$5") (pintype "bidirectional"))
      (node (ref "U6") (pin "S2") (pinfunction "S2_S2") (pintype "bidirectional"))
      (node (ref "U7") (pin "P$3") (pinfunction "S2_P$3") (pintype "bidirectional"))
      (node (ref "V10") (pin "P$1") (pinfunction "P$1_P$1") (pintype "bidirectional"))
      (node (ref "V3") (pin "P$1") (pinfunction "P$1_P$1") (pintype "bidirectional"))
      (node (ref "V4") (pin "P$1") (pinfunction "P$1_P$1") (pintype "bidirectional"))
      (node (ref "V41") (pin "P$1") (pinfunction "P$1_P$1") (pintype "bidirectional"))
      (node (ref "V5") (pin "P$1") (pinfunction "P$1_P$1") (pintype "bidirectional"))
      (node (ref "V6") (pin "P$1") (pinfunction "P$1_P$1") (pintype "bidirectional"))
      (node (ref "V7") (pin "P$1") (pinfunction "P$1_P$1") (pintype "bidirectional"))
      (node (ref "V8") (pin "P$1") (pinfunction "P$1_P$1") (pintype "bidirectional"))
    )
    (net (code "37") (name "Net-(C1-P$1)") (class "Default")
      (node (ref "C1") (pin "1") (pinfunction "P$1_1") (pintype "passive"))
      (node (ref "R1") (pin "1") (pinfunction "1_1") (pintype "passive"))
      (node (ref "U6") (pin "VDD") (pinfunction "VDD_VDD") (pintype "bidirectional"))
    )
    (net (code "38") (name "Net-(C1-P$2)") (class "Default")
      (node (ref "C1") (pin "2") (pinfunction "P$2_2") (pintype "passive"))
      (node (ref "C2") (pin "2") (pinfunction "P$2_2") (pintype "passive"))
      (node (ref "R24") (pin "P$2") (pinfunction "2_P$2") (pintype "passive"))
      (node (ref "R29") (pin "1") (pinfunction "1_1") (pintype "passive"))
      (node (ref "R3") (pin "P$2") (pinfunction "2_P$2") (pintype "passive"))
      (node (ref "R31") (pin "2") (pinfunction "2_2") (pintype "passive"))
      (node (ref "R8") (pin "P$1") (pinfunction "1_P$1") (pintype "passive"))
      (node (ref "U2") (pin "P$1") (pinfunction "-IN_P$1") (pintype "bidirectional"))
      (node (ref "U4") (pin "P$3") (pinfunction "TST_P$3") (pintype "bidirectional"))
      (node (ref "U4") (pin "P$6") (pinfunction "S1_P$6") (pintype "bidirectional"))
      (node (ref "U6") (pin "S1") (pinfunction "S1_S1") (pintype "bidirectional"))
    )
    (net (code "39") (name "Net-(C2-P$1)") (class "Default")
      (node (ref "C2") (pin "1") (pinfunction "P$1_1") (pintype "passive"))
      (node (ref "R20") (pin "1") (pinfunction "1_1") (pintype "passive"))
      (node (ref "U4") (pin "P$5") (pinfunction "VCC_P$5") (pintype "bidirectional"))
    )
    (net (code "40") (name "Net-(C23-P$1)") (class "Default")
      (node (ref "C23") (pin "1") (pinfunction "P$1_1") (pintype "passive"))
      (node (ref "M2") (pin "3") (pinfunction "S_3") (pintype "bidirectional"))
      (node (ref "SW1") (pin "P$5") (pinfunction "OUT_P$5") (pintype "power_in"))
      (node (ref "SW1") (pin "P$6") (pinfunction "OUT_P$6") (pintype "power_in"))
      (node (ref "SW1") (pin "P$7") (pinfunction "OUT_P$7") (pintype "power_in"))
      (node (ref "V21") (pin "P$1") (pinfunction "P$1_P$1") (pintype "bidirectional"))
      (node (ref "V26") (pin "P$1") (pinfunction "P$1_P$1") (pintype "bidirectional"))
    )
    (net (code "41") (name "Net-(C25-P$2)") (class "Default")
      (node (ref "C25") (pin "2") (pinfunction "P$2_2") (pintype "passive"))
      (node (ref "R77") (pin "2") (pinfunction "2_2") (pintype "passive"))
      (node (ref "R78") (pin "2") (pinfunction "2_2") (pintype "passive"))
      (node (ref "SW1") (pin "P$2") (pinfunction "CNTRL_P$2") (pintype "input"))
    )
    (net (code "42") (name "Net-(F1-P$2)") (class "Default")
      (node (ref "F1") (pin "2") (pinfunction "P$2_2") (pintype "passive"))
      (node (ref "R13") (pin "P$2") (pinfunction "2_P$2") (pintype "passive"))
      (node (ref "R22") (pin "P$2") (pinfunction "2_P$2") (pintype "passive"))
      (node (ref "V1") (pin "P$1") (pinfunction "P$1_P$1") (pintype "bidirectional"))
      (node (ref "V37") (pin "P$1") (pinfunction "P$1_P$1") (pintype "bidirectional"))
    )
    (net (code "43") (name "Net-(F5-P$2)") (class "Default")
      (node (ref "D2") (pin "C") (pinfunction "C_C") (pintype "passive"))
      (node (ref "F4") (pin "P$2") (pinfunction "P$2_P$2") (pintype "passive"))
      (node (ref "F5") (pin "2") (pinfunction "P$2_2") (pintype "passive"))
      (node (ref "M2") (pin "2") (pinfunction "D_2") (pintype "bidirectional"))
      (node (ref "R14") (pin "P$2") (pinfunction "2_P$2") (pintype "passive"))
      (node (ref "R16") (pin "P$2") (pinfunction "2_P$2") (pintype "passive"))
      (node (ref "R23") (pin "2") (pinfunction "2_2") (pintype "passive"))
      (node (ref "SW1") (pin "PAD") (pinfunction "VB_PAD") (pintype "power_in"))
      (node (ref "V2") (pin "P$1") (pinfunction "P$1_P$1") (pintype "bidirectional"))
    )
    (net (code "44") (name "Net-(M2-G)") (class "Default")
      (node (ref "M1") (pin "P$5") (pinfunction "D_P$5") (pintype "bidirectional"))
      (node (ref "M1") (pin "P$6") (pinfunction "D_P$6") (pintype "bidirectional"))
      (node (ref "M1") (pin "P$7") (pinfunction "D_P$7") (pintype "bidirectional"))
      (node (ref "M1") (pin "P$8") (pinfunction "D_P$8") (pintype "bidirectional"))
      (node (ref "M1") (pin "PAD") (pinfunction "D_PAD") (pintype "bidirectional"))
      (node (ref "M2") (pin "1") (pinfunction "G_1") (pintype "bidirectional"))
      (node (ref "R23") (pin "1") (pinfunction "1_1") (pintype "passive"))
    )
    (net (code "45") (name "Net-(R2-Pad1)") (class "Default")
      (node (ref "R2") (pin "1") (pinfunction "1_1") (pintype "passive"))
      (node (ref "U6") (pin "VM") (pinfunction "VM_VM") (pintype "bidirectional"))
    )
    (net (code "46") (name "Net-(R26-Pad1)") (class "Default")
      (node (ref "R26") (pin "1") (pinfunction "1_1") (pintype "passive"))
      (node (ref "R29") (pin "2") (pinfunction "2_2") (pintype "passive"))
      (node (ref "U6") (pin "VSS") (pinfunction "VSS_VSS") (pintype "bidirectional"))
    )
    (net (code "47") (name "Net-(R54-1)") (class "Default")
      (node (ref "R54") (pin "P$1") (pinfunction "1_P$1") (pintype "passive"))
      (node (ref "U7") (pin "P$7") (pinfunction "D1_P$7") (pintype "bidirectional"))
      (node (ref "U7") (pin "P$8") (pinfunction "D1_P$8") (pintype "bidirectional"))
    )
    (net (code "48") (name "Net-(R55-1)") (class "Default")
      (node (ref "LIFEPO1") (pin "MINUS") (pinfunction "MINUS_MINUS") (pintype "power_in"))
      (node (ref "LIFEPO2") (pin "PLUS") (pinfunction "PLUS_PLUS") (pintype "power_in"))
      (node (ref "R47") (pin "2") (pinfunction "2_2") (pintype "passive"))
      (node (ref "R55") (pin "P$1") (pinfunction "1_P$1") (pintype "passive"))
      (node (ref "U7") (pin "P$1") (pinfunction "S1_P$1") (pintype "bidirectional"))
      (node (ref "V16") (pin "P$1") (pinfunction "P$1_P$1") (pintype "bidirectional"))
    )
    (net (code "49") (name "Net-(R55-2)") (class "Default")
      (node (ref "R55") (pin "P$2") (pinfunction "2_P$2") (pintype "passive"))
      (node (ref "U7") (pin "P$5") (pinfunction "D2_P$5") (pintype "bidirectional"))
      (node (ref "U7") (pin "P$6") (pinfunction "D2_P$6") (pintype "bidirectional"))
    )
    (net (code "50") (name "Net-(SW1-ISNS)") (class "Default")
      (node (ref "R58") (pin "2") (pinfunction "2_2") (pintype "passive"))
      (node (ref "R79") (pin "2") (pinfunction "2_2") (pintype "passive"))
      (node (ref "SW1") (pin "P$3") (pinfunction "ISNS_P$3") (pintype "output"))
    )
    (net (code "51") (name "Net-(U2-OUT)") (class "Default")
      (node (ref "U2") (pin "P$5") (pinfunction "OUT_P$5") (pintype "bidirectional"))
      (node (ref "V43") (pin "P$1") (pinfunction "P$1_P$1") (pintype "bidirectional"))
    )
    (net (code "52") (name "Net-(U2-VREF1)") (class "Default")
      (node (ref "R10") (pin "2") (pinfunction "2_2") (pintype "passive"))
      (node (ref "R9") (pin "2") (pinfunction "2_2") (pintype "passive"))
      (node (ref "U2") (pin "P$3") (pinfunction "VREF2_P$3") (pintype "bidirectional"))
      (node (ref "U2") (pin "P$7") (pinfunction "VREF1_P$7") (pintype "bidirectional"))
      (node (ref "V12") (pin "P$1") (pinfunction "P$1_P$1") (pintype "bidirectional"))
    )
    (net (code "53") (name "Net-(U3-OUT)") (class "Default")
      (node (ref "U3") (pin "P$5") (pinfunction "OUT_P$5") (pintype "bidirectional"))
      (node (ref "V13") (pin "P$1") (pinfunction "P$1_P$1") (pintype "bidirectional"))
    )
    (net (code "54") (name "Net-(U3-VREF1)") (class "Default")
      (node (ref "R11") (pin "2") (pinfunction "2_2") (pintype "passive"))
      (node (ref "R12") (pin "2") (pinfunction "2_2") (pintype "passive"))
      (node (ref "U3") (pin "P$3") (pinfunction "VREF2_P$3") (pintype "bidirectional"))
      (node (ref "U3") (pin "P$7") (pinfunction "VREF1_P$7") (pintype "bidirectional"))
      (node (ref "V11") (pin "P$1") (pinfunction "P$1_P$1") (pintype "bidirectional"))
    )
    (net (code "55") (name "Net-(U4-CS)") (class "Default")
      (node (ref "R21") (pin "2") (pinfunction "2_2") (pintype "passive"))
      (node (ref "U4") (pin "P$2") (pinfunction "CS_P$2") (pintype "bidirectional"))
    )
    (net (code "56") (name "Net-(U4-VSS)") (class "Default")
      (node (ref "R30") (pin "1") (pinfunction "1_1") (pintype "passive"))
      (node (ref "R31") (pin "1") (pinfunction "1_1") (pintype "passive"))
      (node (ref "U4") (pin "P$4") (pinfunction "VSS_P$4") (pintype "bidirectional"))
    )
    (net (code "57") (name "Net-(U5-FBG)") (class "Default")
      (node (ref "R52") (pin "1") (pinfunction "1_1") (pintype "passive"))
      (node (ref "U5") (pin "P$11") (pinfunction "FBG_P$11") (pintype "bidirectional"))
    )
    (net (code "58") (name "unconnected-(U1-NC-PadP$11)") (class "Default")
      (node (ref "U1") (pin "P$11") (pinfunction "NC_P$11") (pintype "bidirectional"))
    )
    (net (code "59") (name "unconnected-(U2-NC-PadP$4)") (class "Default")
      (node (ref "U2") (pin "P$4") (pinfunction "NC_P$4") (pintype "bidirectional"))
    )
    (net (code "60") (name "unconnected-(U3-NC-PadP$4)") (class "Default")
      (node (ref "U3") (pin "P$4") (pinfunction "NC_P$4") (pintype "bidirectional"))
    )
    (net (code "61") (name "unconnected-(U6-PadNC)") (class "Default")
      (node (ref "U6") (pin "NC") (pinfunction "NC_NC") (pintype "bidirectional"))
    )
  )
)
